# PAGE1.net
KiCad netlist of a schematic drawn in Altium Designer
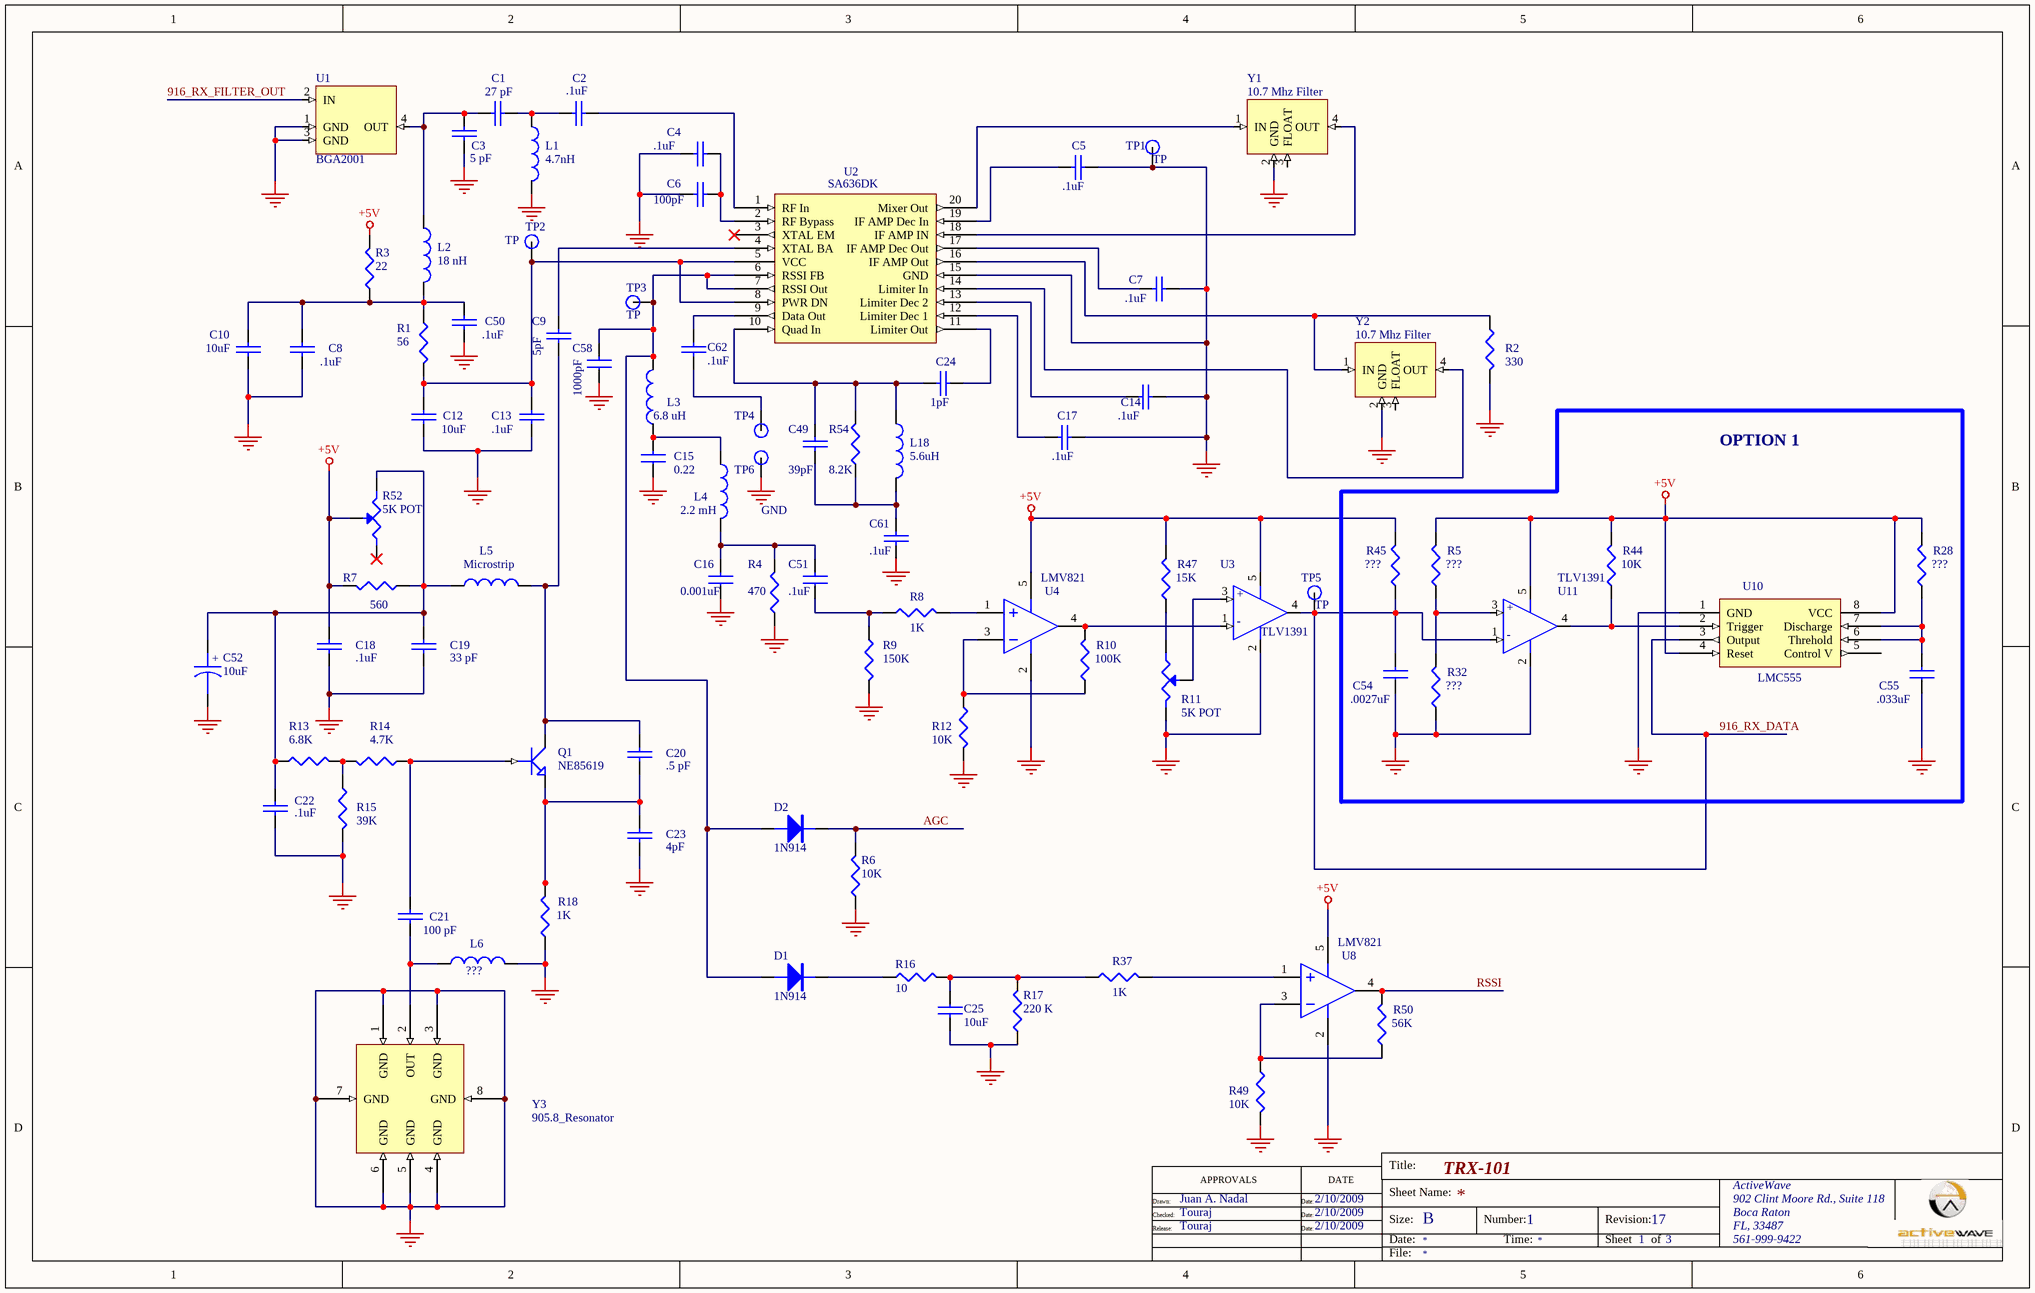
[diagram p0: PAGE1.SCHDOC]

(export (version "E")
  (design (tool "Eeschema 10.0.6"))
  (components
    (comp (ref "C1")
      (value "27 pF")
      (footprint "0603")
      (description "Capacitor")
      (libsource (lib "*") (part "CAP"))
    )
    (comp (ref "C2")
      (value ".1uF")
      (footprint "0603")
      (description "Capacitor")
      (libsource (lib "*") (part "CAP"))
    )
    (comp (ref "C3")
      (value "5 pF")
      (footprint "0603")
      (description "Capacitor")
      (libsource (lib "*") (part "CAP"))
    )
    (comp (ref "C4")
      (value ".1uF")
      (footprint "0603")
      (description "Capacitor")
      (libsource (lib "*") (part "CAP"))
    )
    (comp (ref "C5")
      (value ".1uF")
      (footprint "0603")
      (description "Capacitor")
      (libsource (lib "*") (part "CAP"))
    )
    (comp (ref "C6")
      (value "100pF")
      (footprint "0603")
      (description "Capacitor")
      (libsource (lib "*") (part "CAP"))
    )
    (comp (ref "C7")
      (value ".1uF")
      (footprint "0603")
      (description "Capacitor")
      (libsource (lib "*") (part "CAP"))
    )
    (comp (ref "C8")
      (value ".1uF")
      (footprint "0603")
      (description "Capacitor")
      (libsource (lib "*") (part "CAP"))
    )
    (comp (ref "C9")
      (value "5pF")
      (footprint "0603")
      (description "Capacitor")
      (libsource (lib "*") (part "CAP"))
    )
    (comp (ref "C10")
      (value "10uF")
      (footprint "CAP A CASE")
      (description "Capacitor")
      (libsource (lib "*") (part "CAP"))
    )
    (comp (ref "C12")
      (value "10uF")
      (footprint "CAP A CASE")
      (description "Capacitor")
      (libsource (lib "*") (part "CAP"))
    )
    (comp (ref "C13")
      (value ".1uF")
      (footprint "0603")
      (description "Capacitor")
      (libsource (lib "*") (part "CAP"))
    )
    (comp (ref "C14")
      (value ".1uF")
      (footprint "0603")
      (description "Capacitor")
      (libsource (lib "*") (part "CAP"))
    )
    (comp (ref "C15") (value "0.22") (footprint "0603") (libsource (lib "*") (part "CAP_NP")))
    (comp (ref "C16") (value "0.001uF") (footprint "0603") (libsource (lib "*") (part "CAP_NP")))
    (comp (ref "C17")
      (value ".1uF")
      (footprint "0603")
      (description "Capacitor")
      (libsource (lib "*") (part "CAP"))
    )
    (comp (ref "C18")
      (value ".1uF")
      (footprint "0603")
      (description "Capacitor")
      (libsource (lib "*") (part "CAP"))
    )
    (comp (ref "C19")
      (value "33 pF")
      (footprint "0603")
      (description "Capacitor")
      (libsource (lib "*") (part "CAP"))
    )
    (comp (ref "C20")
      (value ".5 pF")
      (footprint "0603")
      (description "Capacitor")
      (libsource (lib "*") (part "CAP"))
    )
    (comp (ref "C21")
      (value "100 pF")
      (footprint "0603")
      (description "Capacitor")
      (libsource (lib "*") (part "CAP"))
    )
    (comp (ref "C22")
      (value ".1uF")
      (footprint "0603")
      (description "Capacitor")
      (libsource (lib "*") (part "CAP"))
    )
    (comp (ref "C23")
      (value "4pF")
      (footprint "0603")
      (description "Capacitor")
      (libsource (lib "*") (part "CAP"))
    )
    (comp (ref "C24")
      (value "1pF")
      (footprint "0603")
      (description "Capacitor")
      (libsource (lib "*") (part "CAP"))
    )
    (comp (ref "C25") (value "10uF") (footprint "CAP A CASE") (libsource (lib "*") (part "CAP_NP")))
    (comp (ref "C49")
      (value "39pF")
      (footprint "0603")
      (description "Capacitor")
      (libsource (lib "*") (part "CAP"))
    )
    (comp (ref "C50")
      (value ".1uF")
      (footprint "0603")
      (description "Capacitor")
      (libsource (lib "*") (part "CAP"))
    )
    (comp (ref "C51") (value ".1uF") (footprint "0603") (libsource (lib "*") (part "CAP_NP")))
    (comp (ref "C52")
      (value "10uF")
      (footprint "CAP A CASE")
      (description "Capacitor")
      (libsource (lib "*") (part "CAPACITOR POL"))
    )
    (comp (ref "C54") (value ".0027uF") (footprint "0603") (libsource (lib "*") (part "CAP_NP")))
    (comp (ref "C55") (value ".033uF") (footprint "0805") (libsource (lib "*") (part "CAP_NP")))
    (comp (ref "C58") (value "1000pF") (footprint "0603") (libsource (lib "*") (part "CAP_NP")))
    (comp (ref "C61")
      (value ".1uF")
      (footprint "0603")
      (description "Capacitor")
      (libsource (lib "*") (part "CAP"))
    )
    (comp (ref "C62")
      (value ".1uF")
      (footprint "0603")
      (description "Capacitor")
      (libsource (lib "*") (part "CAP"))
    )
    (comp (ref "D1")
      (value "1N914")
      (footprint "SOT23 DIODE")
      (description "Diode")
      (libsource (lib "*") (part "DIODE"))
    )
    (comp (ref "D2")
      (value "1N914")
      (footprint "SOT23 DIODE")
      (description "Diode")
      (libsource (lib "*") (part "DIODE"))
    )
    (comp (ref "L1") (value "4.7nH") (footprint "0603") (libsource (lib "*") (part "INDUCTOR")))
    (comp (ref "L2") (value "18 nH") (footprint "0603") (libsource (lib "*") (part "INDUCTOR")))
    (comp (ref "L3") (value "6.8 uH") (footprint "0805") (libsource (lib "*") (part "INDUCTOR")))
    (comp (ref "L4") (value "2.2 mH") (footprint "COIL TKS5540CT-ND") (libsource (lib "*") (part "INDUCTOR")))
    (comp (ref "L5") (value "Microstrip") (footprint "MICROSTRIP") (libsource (lib "*") (part "INDUCTOR")))
    (comp (ref "L6") (value "???") (footprint "0603") (libsource (lib "*") (part "INDUCTOR")))
    (comp (ref "L18") (value "5.6uH") (footprint "0603") (libsource (lib "*") (part "INDUCTOR")))
    (comp (ref "Q1")
      (value "NE85619")
      (footprint "3 PIN ULTRA SUPER MINI MOLD")
      (description "NPN Transistor")
      (libsource (lib "*") (part "NPN1"))
    )
    (comp (ref "R1") (value "56") (footprint "0603") (libsource (lib "*") (part "R")))
    (comp (ref "R2") (value "330") (footprint "0603") (libsource (lib "*") (part "R")))
    (comp (ref "R3") (value "22") (footprint "0603") (libsource (lib "*") (part "R")))
    (comp (ref "R4") (value "470") (footprint "0603") (libsource (lib "*") (part "R")))
    (comp (ref "R5") (value "???") (footprint "0603") (libsource (lib "*") (part "R")))
    (comp (ref "R6") (value "10K") (footprint "0603") (libsource (lib "*") (part "R")))
    (comp (ref "R7") (value "560") (footprint "0603") (libsource (lib "*") (part "RESISTOR")))
    (comp (ref "R8") (value "1K") (footprint "0603") (libsource (lib "*") (part "R")))
    (comp (ref "R9") (value "150K") (footprint "0603") (libsource (lib "*") (part "R")))
    (comp (ref "R10") (value "100K") (footprint "0603") (libsource (lib "*") (part "R")))
    (comp (ref "R11")
      (value "5K POT")
      (footprint "POT PANA EVN5")
      (description "Potentiometer")
      (libsource (lib "") (part "POT1_1"))
    )
    (comp (ref "R12") (value "10K") (footprint "0603") (libsource (lib "*") (part "R")))
    (comp (ref "R13") (value "6.8K") (footprint "0603") (libsource (lib "*") (part "RESISTOR")))
    (comp (ref "R14") (value "4.7K") (footprint "0603") (libsource (lib "*") (part "RESISTOR")))
    (comp (ref "R15") (value "39K") (footprint "0603") (libsource (lib "*") (part "RESISTOR")))
    (comp (ref "R16") (value "10") (footprint "0603") (libsource (lib "*") (part "R")))
    (comp (ref "R17") (value "220 K") (footprint "0603") (libsource (lib "*") (part "R")))
    (comp (ref "R18") (value "1K") (footprint "0603") (libsource (lib "*") (part "RESISTOR")))
    (comp (ref "R28") (value "???") (footprint "0603") (libsource (lib "*") (part "R")))
    (comp (ref "R32") (value "???") (footprint "0603") (libsource (lib "*") (part "R")))
    (comp (ref "R37") (value "1K") (footprint "0603") (libsource (lib "*") (part "R")))
    (comp (ref "R44") (value "10K") (footprint "0603") (libsource (lib "*") (part "R")))
    (comp (ref "R45") (value "???") (footprint "0603") (libsource (lib "*") (part "R")))
    (comp (ref "R47") (value "15K") (footprint "0603") (libsource (lib "*") (part "R")))
    (comp (ref "R49") (value "10K") (footprint "0603") (libsource (lib "*") (part "R")))
    (comp (ref "R50") (value "56K") (footprint "0603") (libsource (lib "*") (part "R")))
    (comp (ref "R52")
      (value "5K POT")
      (footprint "POT PANA EVN5")
      (description "Potentiometer")
      (libsource (lib "*") (part "POT1"))
    )
    (comp (ref "R54") (value "8.2K") (footprint "0603") (libsource (lib "*") (part "R")))
    (comp (ref "TP1") (value "TP") (footprint "TESTPOINT") (libsource (lib "TRX-101R16") (part "TP")))
    (comp (ref "TP2") (value "TP") (footprint "TESTPOINT") (libsource (lib "TRX-101R16") (part "TP")))
    (comp (ref "TP3") (value "TP") (footprint "TESTPOINT") (libsource (lib "TRX-101R16") (part "TP")))
    (comp (ref "TP4") (value "TP") (footprint "TESTPOINT") (libsource (lib "TRX-101R16") (part "TP")))
    (comp (ref "TP5") (value "TP") (footprint "TESTPOINT") (libsource (lib "TRX-101R16") (part "TP")))
    (comp (ref "TP6") (value "GND") (footprint "TESTPOINT") (libsource (lib "TRX-101R16") (part "TP")))
    (comp (ref "U1") (value "BGA2001") (footprint "SOT343") (libsource (lib "*") (part "BGA2001")))
    (comp (ref "U2") (value "SA636DK") (footprint "SSOP20") (libsource (lib "*") (part "SA636DK")))
    (comp (ref "U3") (value "TLV1391") (footprint "SOT25") (libsource (lib "*") (part "TLV1391")))
    (comp (ref "U4") (value "LMV821") (footprint "SOT25") (libsource (lib "*") (part "OPAMP1")))
    (comp (ref "U8") (value "LMV821") (footprint "SOT25") (libsource (lib "*") (part "OPAMP1")))
    (comp (ref "U10") (value "LMC555") (footprint "SO8 SMALL") (libsource (lib "*") (part "LMC555")))
    (comp (ref "U11") (value "TLV1391") (footprint "SOT25") (libsource (lib "*") (part "TLV1391")))
    (comp (ref "Y1") (value "10.7 Mhz Filter") (footprint "FILTER2") (libsource (lib "*") (part "FILTER2")))
    (comp (ref "Y2") (value "10.7 Mhz Filter") (footprint "FILTER2") (libsource (lib "*") (part "FILTER2")))
    (comp (ref "Y3")
      (value "905.8_Resonator")
      (footprint "RESONATOR")
      (libsource (lib "TRX-101_16") (part "RESONATOR2"))
    )
  )
  (nets
    (net (code "1") (name "+5V") (class "Default")
      (node (ref "C18") (pin "1") (pinfunction "1_1") (pintype "passive"))
      (node (ref "R28") (pin "2") (pinfunction "2_2") (pintype "passive"))
      (node (ref "R3") (pin "2") (pinfunction "2_2") (pintype "passive"))
      (node (ref "R44") (pin "2") (pinfunction "2_2") (pintype "passive"))
      (node (ref "R45") (pin "2") (pinfunction "2_2") (pintype "passive"))
      (node (ref "R47") (pin "2") (pinfunction "2_2") (pintype "passive"))
      (node (ref "R5") (pin "2") (pinfunction "2_2") (pintype "passive"))
      (node (ref "R52") (pin "2") (pinfunction "2_2") (pintype "passive"))
      (node (ref "R7") (pin "2") (pinfunction "2_2") (pintype "passive"))
      (node (ref "U10") (pin "4") (pinfunction "Reset_4") (pintype "input"))
      (node (ref "U10") (pin "8") (pinfunction "VCC_8") (pintype "power_in"))
      (node (ref "U11") (pin "5") (pinfunction "VDD_5") (pintype "power_in"))
      (node (ref "U3") (pin "5") (pinfunction "VDD_5") (pintype "power_in"))
      (node (ref "U4") (pin "5") (pinfunction "5_5") (pintype "passive"))
      (node (ref "U8") (pin "5") (pinfunction "5_5") (pintype "passive"))
    )
    (net (code "2") (name "/916_RX_DATA") (class "Default")
      (node (ref "C54") (pin "2") (pinfunction "2_2") (pintype "passive"))
      (node (ref "R45") (pin "1") (pinfunction "1_1") (pintype "passive"))
      (node (ref "TP5") (pin "1") (pinfunction "TP_1") (pintype "passive"))
      (node (ref "U10") (pin "3") (pinfunction "Output_3") (pintype "output"))
      (node (ref "U11") (pin "1") (pinfunction "-_1") (pintype "input"))
      (node (ref "U3") (pin "4") (pinfunction "OUT_4") (pintype "open_collector"))
    )
    (net (code "3") (name "/916_RX_FILTER_OUT") (class "Default")
      (node (ref "U1") (pin "2") (pinfunction "IN_2") (pintype "input"))
    )
    (net (code "4") (name "/AGC") (class "Default")
      (node (ref "D2") (pin "K") (pinfunction "K_K") (pintype "passive"))
      (node (ref "R6") (pin "1") (pinfunction "1_1") (pintype "passive"))
    )
    (net (code "5") (name "/RSSI") (class "Default")
      (node (ref "R50") (pin "2") (pinfunction "2_2") (pintype "passive"))
      (node (ref "U8") (pin "4") (pinfunction "4_4") (pintype "passive"))
    )
    (net (code "6") (name "GND_SIGNAL") (class "Default")
      (node (ref "C10") (pin "2") (pinfunction "2_2") (pintype "passive"))
      (node (ref "C12") (pin "2") (pinfunction "2_2") (pintype "passive"))
      (node (ref "C13") (pin "2") (pinfunction "2_2") (pintype "passive"))
      (node (ref "C14") (pin "2") (pinfunction "2_2") (pintype "passive"))
      (node (ref "C15") (pin "1") (pinfunction "1_1") (pintype "passive"))
      (node (ref "C16") (pin "1") (pinfunction "1_1") (pintype "passive"))
      (node (ref "C17") (pin "2") (pinfunction "2_2") (pintype "passive"))
      (node (ref "C18") (pin "2") (pinfunction "2_2") (pintype "passive"))
      (node (ref "C19") (pin "2") (pinfunction "2_2") (pintype "passive"))
      (node (ref "C22") (pin "2") (pinfunction "2_2") (pintype "passive"))
      (node (ref "C23") (pin "2") (pinfunction "2_2") (pintype "passive"))
      (node (ref "C25") (pin "2") (pinfunction "2_2") (pintype "passive"))
      (node (ref "C3") (pin "2") (pinfunction "2_2") (pintype "passive"))
      (node (ref "C4") (pin "1") (pinfunction "1_1") (pintype "passive"))
      (node (ref "C5") (pin "2") (pinfunction "2_2") (pintype "passive"))
      (node (ref "C50") (pin "2") (pinfunction "2_2") (pintype "passive"))
      (node (ref "C52") (pin "2") (pinfunction "2_2") (pintype "passive"))
      (node (ref "C54") (pin "1") (pinfunction "1_1") (pintype "passive"))
      (node (ref "C55") (pin "1") (pinfunction "1_1") (pintype "passive"))
      (node (ref "C58") (pin "1") (pinfunction "1_1") (pintype "passive"))
      (node (ref "C6") (pin "1") (pinfunction "1_1") (pintype "passive"))
      (node (ref "C61") (pin "2") (pinfunction "2_2") (pintype "passive"))
      (node (ref "C7") (pin "2") (pinfunction "2_2") (pintype "passive"))
      (node (ref "C8") (pin "2") (pinfunction "2_2") (pintype "passive"))
      (node (ref "L1") (pin "2") (pinfunction "2_2") (pintype "passive"))
      (node (ref "L6") (pin "2") (pinfunction "2_2") (pintype "passive"))
      (node (ref "R11") (pin "3") (pinfunction "3_3") (pintype "passive"))
      (node (ref "R12") (pin "2") (pinfunction "2_2") (pintype "passive"))
      (node (ref "R15") (pin "2") (pinfunction "2_2") (pintype "passive"))
      (node (ref "R17") (pin "2") (pinfunction "2_2") (pintype "passive"))
      (node (ref "R18") (pin "1") (pinfunction "1_1") (pintype "passive"))
      (node (ref "R2") (pin "2") (pinfunction "2_2") (pintype "passive"))
      (node (ref "R32") (pin "1") (pinfunction "1_1") (pintype "passive"))
      (node (ref "R4") (pin "1") (pinfunction "1_1") (pintype "passive"))
      (node (ref "R49") (pin "2") (pinfunction "2_2") (pintype "passive"))
      (node (ref "R6") (pin "2") (pinfunction "2_2") (pintype "passive"))
      (node (ref "R9") (pin "2") (pinfunction "2_2") (pintype "passive"))
      (node (ref "TP1") (pin "1") (pinfunction "TP_1") (pintype "passive"))
      (node (ref "TP6") (pin "1") (pinfunction "TP_1") (pintype "passive"))
      (node (ref "U1") (pin "1") (pinfunction "GND_1") (pintype "input"))
      (node (ref "U1") (pin "3") (pinfunction "GND_3") (pintype "input"))
      (node (ref "U10") (pin "1") (pinfunction "GND_1") (pintype "power_in"))
      (node (ref "U11") (pin "2") (pinfunction "VSS_2") (pintype "power_in"))
      (node (ref "U2") (pin "15") (pinfunction "GND_15") (pintype "input"))
      (node (ref "U3") (pin "2") (pinfunction "VSS_2") (pintype "power_in"))
      (node (ref "U4") (pin "2") (pinfunction "2_2") (pintype "passive"))
      (node (ref "U8") (pin "2") (pinfunction "2_2") (pintype "passive"))
      (node (ref "Y1") (pin "2") (pinfunction "GND_2") (pintype "input"))
      (node (ref "Y2") (pin "2") (pinfunction "GND_2") (pintype "input"))
      (node (ref "Y3") (pin "1") (pinfunction "GND_1") (pintype "input"))
      (node (ref "Y3") (pin "3") (pinfunction "GND_3") (pintype "input"))
      (node (ref "Y3") (pin "4") (pinfunction "GND_4") (pintype "input"))
      (node (ref "Y3") (pin "5") (pinfunction "GND_5") (pintype "input"))
      (node (ref "Y3") (pin "6") (pinfunction "GND_6") (pintype "input"))
      (node (ref "Y3") (pin "7") (pinfunction "GND_7") (pintype "input"))
      (node (ref "Y3") (pin "8") (pinfunction "GND_8") (pintype "input"))
    )
    (net (code "7") (name "Net-(C1-Pad2)") (class "Default")
      (node (ref "C1") (pin "2") (pinfunction "2_2") (pintype "passive"))
      (node (ref "C2") (pin "1") (pinfunction "1_1") (pintype "passive"))
      (node (ref "L1") (pin "1") (pinfunction "1_1") (pintype "passive"))
    )
    (net (code "8") (name "Net-(C10-Pad1)") (class "Default")
      (node (ref "C10") (pin "1") (pinfunction "1_1") (pintype "passive"))
      (node (ref "C50") (pin "1") (pinfunction "1_1") (pintype "passive"))
      (node (ref "C8") (pin "1") (pinfunction "1_1") (pintype "passive"))
      (node (ref "L2") (pin "2") (pinfunction "2_2") (pintype "passive"))
      (node (ref "R1") (pin "1") (pinfunction "1_1") (pintype "passive"))
      (node (ref "R3") (pin "1") (pinfunction "1_1") (pintype "passive"))
    )
    (net (code "9") (name "Net-(C15-Pad2)") (class "Default")
      (node (ref "C15") (pin "2") (pinfunction "2_2") (pintype "passive"))
      (node (ref "L3") (pin "1") (pinfunction "1_1") (pintype "passive"))
      (node (ref "L4") (pin "1") (pinfunction "1_1") (pintype "passive"))
    )
    (net (code "10") (name "Net-(C16-Pad2)") (class "Default")
      (node (ref "C16") (pin "2") (pinfunction "2_2") (pintype "passive"))
      (node (ref "C51") (pin "2") (pinfunction "2_2") (pintype "passive"))
      (node (ref "L4") (pin "2") (pinfunction "2_2") (pintype "passive"))
      (node (ref "R4") (pin "2") (pinfunction "2_2") (pintype "passive"))
    )
    (net (code "11") (name "Net-(C19-Pad1)") (class "Default")
      (node (ref "C19") (pin "1") (pinfunction "1_1") (pintype "passive"))
      (node (ref "C22") (pin "1") (pinfunction "1_1") (pintype "passive"))
      (node (ref "C52") (pin "1") (pinfunction "1_1") (pintype "passive"))
      (node (ref "L5") (pin "1") (pinfunction "1_1") (pintype "passive"))
      (node (ref "R13") (pin "1") (pinfunction "1_1") (pintype "passive"))
      (node (ref "R52") (pin "1") (pinfunction "1_1") (pintype "passive"))
      (node (ref "R7") (pin "1") (pinfunction "1_1") (pintype "passive"))
    )
    (net (code "12") (name "Net-(C20-Pad1)") (class "Default")
      (node (ref "C20") (pin "1") (pinfunction "1_1") (pintype "passive"))
      (node (ref "C9") (pin "1") (pinfunction "1_1") (pintype "passive"))
      (node (ref "L5") (pin "2") (pinfunction "2_2") (pintype "passive"))
      (node (ref "Q1") (pin "C") (pinfunction "C_C") (pintype "passive"))
    )
    (net (code "13") (name "Net-(C20-Pad2)") (class "Default")
      (node (ref "C20") (pin "2") (pinfunction "2_2") (pintype "passive"))
      (node (ref "C23") (pin "1") (pinfunction "1_1") (pintype "passive"))
      (node (ref "Q1") (pin "E") (pinfunction "E_E") (pintype "passive"))
      (node (ref "R18") (pin "2") (pinfunction "2_2") (pintype "passive"))
    )
    (net (code "14") (name "Net-(C21-Pad1)") (class "Default")
      (node (ref "C21") (pin "1") (pinfunction "1_1") (pintype "passive"))
      (node (ref "Q1") (pin "B") (pinfunction "B_B") (pintype "input"))
      (node (ref "R14") (pin "1") (pinfunction "1_1") (pintype "passive"))
    )
    (net (code "15") (name "Net-(C25-Pad1)") (class "Default")
      (node (ref "C25") (pin "1") (pinfunction "1_1") (pintype "passive"))
      (node (ref "R16") (pin "1") (pinfunction "1_1") (pintype "passive"))
      (node (ref "R17") (pin "1") (pinfunction "1_1") (pintype "passive"))
      (node (ref "R37") (pin "1") (pinfunction "1_1") (pintype "passive"))
    )
    (net (code "16") (name "Net-(C49-Pad2)") (class "Default")
      (node (ref "C49") (pin "2") (pinfunction "2_2") (pintype "passive"))
      (node (ref "C61") (pin "1") (pinfunction "1_1") (pintype "passive"))
      (node (ref "L18") (pin "2") (pinfunction "2_2") (pintype "passive"))
      (node (ref "R54") (pin "1") (pinfunction "1_1") (pintype "passive"))
    )
    (net (code "17") (name "Net-(C51-Pad1)") (class "Default")
      (node (ref "C51") (pin "1") (pinfunction "1_1") (pintype "passive"))
      (node (ref "R8") (pin "1") (pinfunction "1_1") (pintype "passive"))
      (node (ref "R9") (pin "1") (pinfunction "1_1") (pintype "passive"))
    )
    (net (code "18") (name "Net-(D1-PadK)") (class "Default")
      (node (ref "D1") (pin "K") (pinfunction "K_K") (pintype "passive"))
      (node (ref "R16") (pin "2") (pinfunction "2_2") (pintype "passive"))
    )
    (net (code "19") (name "Net-(R8-Pad2)") (class "Default")
      (node (ref "R8") (pin "2") (pinfunction "2_2") (pintype "passive"))
      (node (ref "U4") (pin "1") (pinfunction "1_1") (pintype "passive"))
    )
    (net (code "20") (name "Net-(R10-Pad1)") (class "Default")
      (node (ref "R10") (pin "1") (pinfunction "1_1") (pintype "passive"))
      (node (ref "R12") (pin "1") (pinfunction "1_1") (pintype "passive"))
      (node (ref "U4") (pin "3") (pinfunction "3_3") (pintype "passive"))
    )
    (net (code "21") (name "Net-(R11-Pad1)") (class "Default")
      (node (ref "R11") (pin "1") (pinfunction "1_1") (pintype "passive"))
      (node (ref "R47") (pin "1") (pinfunction "1_1") (pintype "passive"))
    )
    (net (code "22") (name "Net-(R13-Pad2)") (class "Default")
      (node (ref "R13") (pin "2") (pinfunction "2_2") (pintype "passive"))
      (node (ref "R14") (pin "2") (pinfunction "2_2") (pintype "passive"))
      (node (ref "R15") (pin "1") (pinfunction "1_1") (pintype "passive"))
    )
    (net (code "23") (name "Net-(R37-Pad2)") (class "Default")
      (node (ref "R37") (pin "2") (pinfunction "2_2") (pintype "passive"))
      (node (ref "U8") (pin "1") (pinfunction "1_1") (pintype "passive"))
    )
    (net (code "24") (name "Net-(R49-Pad1)") (class "Default")
      (node (ref "R49") (pin "1") (pinfunction "1_1") (pintype "passive"))
      (node (ref "R50") (pin "1") (pinfunction "1_1") (pintype "passive"))
      (node (ref "U8") (pin "3") (pinfunction "3_3") (pintype "passive"))
    )
    (net (code "25") (name "Net-(TP2-TP)") (class "Default")
      (node (ref "C12") (pin "1") (pinfunction "1_1") (pintype "passive"))
      (node (ref "C13") (pin "1") (pinfunction "1_1") (pintype "passive"))
      (node (ref "R1") (pin "2") (pinfunction "2_2") (pintype "passive"))
      (node (ref "TP2") (pin "1") (pinfunction "TP_1") (pintype "passive"))
      (node (ref "U2") (pin "5") (pinfunction "VCC_5") (pintype "power_in"))
      (node (ref "U2") (pin "8") (pinfunction "PWR_DN_8") (pintype "input"))
    )
    (net (code "26") (name "Net-(TP3-TP)") (class "Default")
      (node (ref "C58") (pin "2") (pinfunction "2_2") (pintype "passive"))
      (node (ref "D1") (pin "A") (pinfunction "A_A") (pintype "passive"))
      (node (ref "D2") (pin "A") (pinfunction "A_A") (pintype "passive"))
      (node (ref "L3") (pin "2") (pinfunction "2_2") (pintype "passive"))
      (node (ref "TP3") (pin "1") (pinfunction "TP_1") (pintype "passive"))
      (node (ref "U2") (pin "6") (pinfunction "RSSI_FB_6") (pintype "input"))
      (node (ref "U2") (pin "7") (pinfunction "RSSI_Out_7") (pintype "output"))
    )
    (net (code "27") (name "Net-(TP4-TP)") (class "Default")
      (node (ref "C62") (pin "1") (pinfunction "1_1") (pintype "passive"))
      (node (ref "TP4") (pin "1") (pinfunction "TP_1") (pintype "passive"))
    )
    (net (code "28") (name "Net-(U1-OUT)") (class "Default")
      (node (ref "C1") (pin "1") (pinfunction "1_1") (pintype "passive"))
      (node (ref "C3") (pin "1") (pinfunction "1_1") (pintype "passive"))
      (node (ref "L2") (pin "1") (pinfunction "1_1") (pintype "passive"))
      (node (ref "U1") (pin "4") (pinfunction "OUT_4") (pintype "input"))
    )
    (net (code "29") (name "Net-(U2-Data_Out)") (class "Default")
      (node (ref "C62") (pin "2") (pinfunction "2_2") (pintype "passive"))
      (node (ref "U2") (pin "9") (pinfunction "Data_Out_9") (pintype "output"))
    )
    (net (code "30") (name "Net-(U2-IF_AMP_Dec_In)") (class "Default")
      (node (ref "C5") (pin "1") (pinfunction "1_1") (pintype "passive"))
      (node (ref "U2") (pin "19") (pinfunction "IF_AMP_Dec_In_19") (pintype "input"))
    )
    (net (code "31") (name "Net-(U2-IF_AMP_Dec_Out)") (class "Default")
      (node (ref "C7") (pin "1") (pinfunction "1_1") (pintype "passive"))
      (node (ref "U2") (pin "17") (pinfunction "IF_AMP_Dec_Out_17") (pintype "output"))
    )
    (net (code "32") (name "Net-(U2-IF_AMP_IN)") (class "Default")
      (node (ref "U2") (pin "18") (pinfunction "IF_AMP_IN_18") (pintype "input"))
      (node (ref "Y1") (pin "4") (pinfunction "OUT_4") (pintype "input"))
    )
    (net (code "33") (name "Net-(U2-IF_AMP_Out)") (class "Default")
      (node (ref "R2") (pin "1") (pinfunction "1_1") (pintype "passive"))
      (node (ref "U2") (pin "16") (pinfunction "IF_AMP_Out_16") (pintype "output"))
      (node (ref "Y2") (pin "1") (pinfunction "IN_1") (pintype "input"))
    )
    (net (code "34") (name "Net-(U2-Limiter_Dec_1)") (class "Default")
      (node (ref "C17") (pin "1") (pinfunction "1_1") (pintype "passive"))
      (node (ref "U2") (pin "12") (pinfunction "Limiter_Dec_1_12") (pintype "input"))
    )
    (net (code "35") (name "Net-(U2-Limiter_Dec_2)") (class "Default")
      (node (ref "C14") (pin "1") (pinfunction "1_1") (pintype "passive"))
      (node (ref "U2") (pin "13") (pinfunction "Limiter_Dec_2_13") (pintype "input"))
    )
    (net (code "36") (name "Net-(U2-Limiter_In)") (class "Default")
      (node (ref "U2") (pin "14") (pinfunction "Limiter_In_14") (pintype "input"))
      (node (ref "Y2") (pin "4") (pinfunction "OUT_4") (pintype "input"))
    )
    (net (code "37") (name "Net-(U2-Limiter_Out)") (class "Default")
      (node (ref "C24") (pin "2") (pinfunction "2_2") (pintype "passive"))
      (node (ref "U2") (pin "11") (pinfunction "Limiter_Out_11") (pintype "output"))
    )
    (net (code "38") (name "Net-(U2-Mixer_Out)") (class "Default")
      (node (ref "U2") (pin "20") (pinfunction "Mixer_Out_20") (pintype "output"))
      (node (ref "Y1") (pin "1") (pinfunction "IN_1") (pintype "input"))
    )
    (net (code "39") (name "Net-(U2-Quad_In)") (class "Default")
      (node (ref "C24") (pin "1") (pinfunction "1_1") (pintype "passive"))
      (node (ref "C49") (pin "1") (pinfunction "1_1") (pintype "passive"))
      (node (ref "L18") (pin "1") (pinfunction "1_1") (pintype "passive"))
      (node (ref "R54") (pin "2") (pinfunction "2_2") (pintype "passive"))
      (node (ref "U2") (pin "10") (pinfunction "Quad_In_10") (pintype "input"))
    )
    (net (code "40") (name "Net-(U2-RF_Bypass)") (class "Default")
      (node (ref "C4") (pin "2") (pinfunction "2_2") (pintype "passive"))
      (node (ref "C6") (pin "2") (pinfunction "2_2") (pintype "passive"))
      (node (ref "U2") (pin "2") (pinfunction "RF_Bypass_2") (pintype "input"))
    )
    (net (code "41") (name "Net-(U2-RF_In)") (class "Default")
      (node (ref "C2") (pin "2") (pinfunction "2_2") (pintype "passive"))
      (node (ref "U2") (pin "1") (pinfunction "RF_In_1") (pintype "input"))
    )
    (net (code "42") (name "Net-(U2-XTAL_BA)") (class "Default")
      (node (ref "C9") (pin "2") (pinfunction "2_2") (pintype "passive"))
      (node (ref "U2") (pin "4") (pinfunction "XTAL_BA_4") (pintype "input"))
    )
    (net (code "43") (name "Net-(U3-+)") (class "Default")
      (node (ref "R11") (pin "2") (pinfunction "2_2") (pintype "passive"))
      (node (ref "U3") (pin "3") (pinfunction "+_3") (pintype "input"))
    )
    (net (code "44") (name "Net-(U3--)") (class "Default")
      (node (ref "R10") (pin "2") (pinfunction "2_2") (pintype "passive"))
      (node (ref "U3") (pin "1") (pinfunction "-_1") (pintype "input"))
      (node (ref "U4") (pin "4") (pinfunction "4_4") (pintype "passive"))
    )
    (net (code "45") (name "Net-(U10-Discharge)") (class "Default")
      (node (ref "C55") (pin "2") (pinfunction "2_2") (pintype "passive"))
      (node (ref "R28") (pin "1") (pinfunction "1_1") (pintype "passive"))
      (node (ref "U10") (pin "6") (pinfunction "Threhold_6") (pintype "input"))
      (node (ref "U10") (pin "7") (pinfunction "Discharge_7") (pintype "input"))
    )
    (net (code "46") (name "Net-(U10-Trigger)") (class "Default")
      (node (ref "R44") (pin "1") (pinfunction "1_1") (pintype "passive"))
      (node (ref "U10") (pin "2") (pinfunction "Trigger_2") (pintype "input"))
      (node (ref "U11") (pin "4") (pinfunction "OUT_4") (pintype "open_collector"))
    )
    (net (code "47") (name "Net-(U11-+)") (class "Default")
      (node (ref "R32") (pin "2") (pinfunction "2_2") (pintype "passive"))
      (node (ref "R5") (pin "1") (pinfunction "1_1") (pintype "passive"))
      (node (ref "U11") (pin "3") (pinfunction "+_3") (pintype "input"))
    )
    (net (code "48") (name "Net-(Y3-OUT)") (class "Default")
      (node (ref "C21") (pin "2") (pinfunction "2_2") (pintype "passive"))
      (node (ref "L6") (pin "1") (pinfunction "1_1") (pintype "passive"))
      (node (ref "Y3") (pin "2") (pinfunction "OUT_2") (pintype "input"))
    )
    (net (code "49") (name "unconnected-(R52-Pad3)") (class "Default")
      (node (ref "R52") (pin "3") (pinfunction "3_3") (pintype "passive+no_connect"))
    )
    (net (code "50") (name "unconnected-(U2-XTAL_EM-Pad3)") (class "Default")
      (node (ref "U2") (pin "3") (pinfunction "XTAL_EM_3") (pintype "output+no_connect"))
    )
    (net (code "51") (name "unconnected-(U10-Control_V-Pad5)") (class "Default")
      (node (ref "U10") (pin "5") (pinfunction "Control_V_5") (pintype "output"))
    )
    (net (code "52") (name "unconnected-(Y1-FLOAT-Pad3)") (class "Default")
      (node (ref "Y1") (pin "3") (pinfunction "FLOAT_3") (pintype "input"))
    )
    (net (code "53") (name "unconnected-(Y2-FLOAT-Pad3)") (class "Default")
      (node (ref "Y2") (pin "3") (pinfunction "FLOAT_3") (pintype "input"))
    )
  )
)
